# analog_channel.net
KiCad netlist of a schematic drawn in Altium Designer
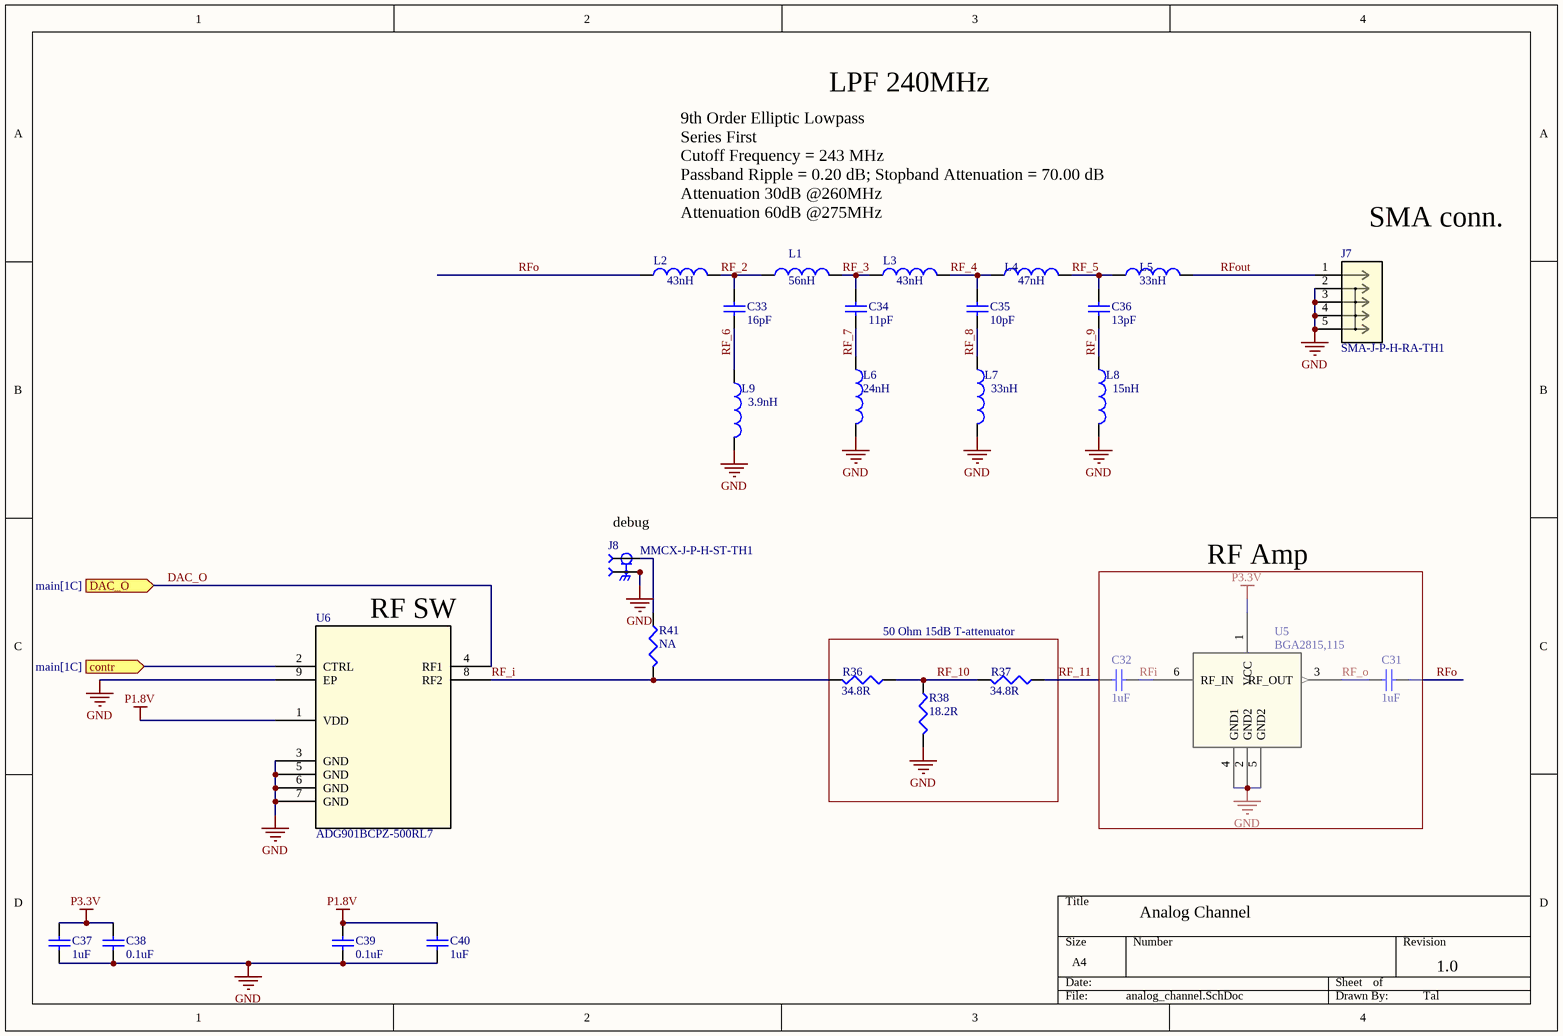
[diagram p0: analog_channel.SchDoc]

(export (version "E")
  (design (tool "Eeschema 10.0.6"))
  (components
    (comp (ref "C31")
      (value "1uF 25V")
      (footprint "Landa_PCB:C0402")
      (description "CAP CER 1uF 25V X5R 0402")
      (fields
        (field (name "MANUFACTURER PART NUMBER") "C1005C0G1H6R8D")
        (field (name "MANUFACTURER") "TDK Corporation")
        (field (name "CAPACITANCE") "1uF")
      )
      (libsource (lib "L_SCH_C") (part "CAP CER 6.8pF 50V NP0 0402"))
    )
    (comp (ref "C32")
      (value "1uF 25V")
      (footprint "Landa_PCB:C0402")
      (description "CAP CER 1uF 25V X5R 0402")
      (fields
        (field (name "MANUFACTURER PART NUMBER") "C1005C0G1H6R8D")
        (field (name "MANUFACTURER") "TDK Corporation")
        (field (name "CAPACITANCE") "1uF")
      )
      (libsource (lib "L_SCH_C") (part "CAP CER 6.8pF 50V NP0 0402"))
    )
    (comp (ref "C33")
      (value "16pF 50V")
      (footprint "Landa_PCB:C0402")
      (description "CAP CER 16PF 50V 5% NP0 0402")
      (fields
        (field (name "MANUFACTURER") "TDK Corporation")
        (field (name "MANUFACTURER PART NUMBER") "C1005C0G1H200J")
        (field (name "CAPACITANCE") "16pF")
      )
      (libsource (lib "L_SCH_C") (part "CAP CER 20pF 50V 5% NP0 0402"))
    )
    (comp (ref "C34")
      (value "11pF 50V")
      (footprint "Landa_PCB:C0402")
      (description "CAP CER 11PF 50V 5% NP0 0402")
      (fields
        (field (name "MANUFACTURER") "TDK Corporation")
        (field (name "MANUFACTURER PART NUMBER") "C1005C0G1H200J")
        (field (name "CAPACITANCE") "11pF")
      )
      (libsource (lib "L_SCH_C") (part "CAP CER 20pF 50V 5% NP0 0402"))
    )
    (comp (ref "C35")
      (value "10pF 50V")
      (footprint "Landa_PCB:C0402")
      (description "CAP CER 10PF 50V 5% NP0 0402")
      (fields
        (field (name "MANUFACTURER") "TDK Corporation")
        (field (name "MANUFACTURER PART NUMBER") "C1005C0G1H200J")
        (field (name "CAPACITANCE") "10pF")
      )
      (libsource (lib "L_SCH_C") (part "CAP CER 20pF 50V 5% NP0 0402"))
    )
    (comp (ref "C36")
      (value "13pF 50V")
      (footprint "Landa_PCB:C0402")
      (description "CAP CER 13PF 50V 5% NP0 0402")
      (fields
        (field (name "MANUFACTURER") "TDK Corporation")
        (field (name "MANUFACTURER PART NUMBER") "C1005C0G1H200J")
        (field (name "CAPACITANCE") "13pF")
      )
      (libsource (lib "L_SCH_C") (part "CAP CER 20pF 50V 5% NP0 0402"))
    )
    (comp (ref "C37")
      (value "1uF 25V")
      (footprint "Landa_PCB:C0402")
      (description "CAP CER 1uF 25V X5R 0402")
      (fields
        (field (name "MANUFACTURER PART NUMBER") "C1005C0G1H6R8D")
        (field (name "MANUFACTURER") "TDK Corporation")
        (field (name "CAPACITANCE") "1uF")
      )
      (libsource (lib "L_SCH_C") (part "CAP CER 6.8pF 50V NP0 0402"))
    )
    (comp (ref "C38")
      (value "0.1uF 50V")
      (footprint "Landa_PCB:C0402")
      (description "CAP CER 0.1uF 50V NP0 0402")
      (fields
        (field (name "MANUFACTURER PART NUMBER") "C1005C0G1H6R8D")
        (field (name "MANUFACTURER") "TDK Corporation")
        (field (name "CAPACITANCE") "0.1uF")
      )
      (libsource (lib "L_SCH_C") (part "CAP CER 6.8pF 50V NP0 0402"))
    )
    (comp (ref "C39")
      (value "0.1uF 50V")
      (footprint "Landa_PCB:C0402")
      (description "CAP CER 0.1uF 50V NP0 0402")
      (fields
        (field (name "MANUFACTURER PART NUMBER") "C1005C0G1H6R8D")
        (field (name "MANUFACTURER") "TDK Corporation")
        (field (name "CAPACITANCE") "0.1uF")
      )
      (libsource (lib "L_SCH_C") (part "CAP CER 6.8pF 50V NP0 0402"))
    )
    (comp (ref "C40")
      (value "1uF 25V")
      (footprint "Landa_PCB:C0402")
      (description "CAP CER 1uF 25V X5R 0402")
      (fields
        (field (name "MANUFACTURER PART NUMBER") "C1005C0G1H6R8D")
        (field (name "MANUFACTURER") "TDK Corporation")
        (field (name "CAPACITANCE") "1uF")
      )
      (libsource (lib "L_SCH_C") (part "CAP CER 6.8pF 50V NP0 0402"))
    )
    (comp (ref "J7")
      (value "SMA-J-P-H-RA-TH1")
      (footprint "CONN_SMA-J-P-H-RA-TH1_SAI")
      (description "No Description Available")
      (fields (field (name "COPYRIGHT") "Copyright (C) 2023 Ultra Librarian. All rights reserved."))
      (libsource (lib "SMA-J-P-H-RA-TH1") (part "SMA-J-P-H-RA-TH1"))
    )
    (comp (ref "J8")
      (value "MMCX-J-P-H-ST-TH1")
      (footprint "SAMTEC_MMCX-J-P-H-ST-TH1")
      (description "MMCX STRAIGHT, THROUGH HOLE JACK- 50 OHM")
      (fields (field (name "MF") "Samtec"))
      (libsource (lib "MMCX-J-P-H-ST-TH1") (part "MMCX-J-P-H-ST-TH1"))
    )
    (comp (ref "L1")
      (value "56nH")
      (footprint "0402-A")
      (description "Inductor")
      (fields (field (name "PUBLISHER") "Altium Limited"))
      (libsource (lib "Miscellaneous Devices") (part "Inductor"))
    )
    (comp (ref "L2")
      (value "43nH")
      (footprint "0402-A")
      (description "Inductor")
      (fields (field (name "PUBLISHER") "Altium Limited"))
      (libsource (lib "Miscellaneous Devices") (part "Inductor"))
    )
    (comp (ref "L3")
      (value "43nH")
      (footprint "0402-A")
      (description "Inductor")
      (fields (field (name "PUBLISHER") "Altium Limited"))
      (libsource (lib "Miscellaneous Devices") (part "Inductor"))
    )
    (comp (ref "L4")
      (value "47nH")
      (footprint "0402-A")
      (description "Inductor")
      (fields (field (name "PUBLISHER") "Altium Limited"))
      (libsource (lib "Miscellaneous Devices") (part "Inductor"))
    )
    (comp (ref "L5")
      (value "33nH")
      (footprint "0402-A")
      (description "Inductor")
      (fields (field (name "PUBLISHER") "Altium Limited"))
      (libsource (lib "Miscellaneous Devices") (part "Inductor"))
    )
    (comp (ref "L6")
      (value "24nH")
      (footprint "0402-A")
      (description "Inductor")
      (fields (field (name "PUBLISHER") "Altium Limited"))
      (libsource (lib "Miscellaneous Devices") (part "Inductor"))
    )
    (comp (ref "L7")
      (value "33nH")
      (footprint "0402-A")
      (description "Inductor")
      (fields (field (name "PUBLISHER") "Altium Limited"))
      (libsource (lib "Miscellaneous Devices") (part "Inductor"))
    )
    (comp (ref "L8")
      (value "15nH")
      (footprint "0402-A")
      (description "Inductor")
      (fields (field (name "PUBLISHER") "Altium Limited"))
      (libsource (lib "Miscellaneous Devices") (part "Inductor"))
    )
    (comp (ref "L9")
      (value "3.9nH")
      (footprint "0402-A")
      (description "Inductor")
      (fields (field (name "PUBLISHER") "Altium Limited"))
      (libsource (lib "Miscellaneous Devices") (part "Inductor"))
    )
    (comp (ref "R36")
      (value "34.8R")
      (footprint "r0402")
      (description "RES 34.8 OHM 1/10W 1% 0402 SMD")
      (fields
        (field (name "MANUFACTURER PART NUMBER") "ERJ-2RKF1000X")
        (field (name "MANUFACTURER") "Panasonic Electronic Components")
      )
      (libsource (lib "L_SCH_R") (part "RES 100 OHM 1/10W 1% 0402 SMD"))
    )
    (comp (ref "R37")
      (value "34.8R")
      (footprint "r0402")
      (description "RES 34.8 OHM 1/10W 1% 0402 SMD")
      (fields
        (field (name "MANUFACTURER PART NUMBER") "ERJ-2RKF1000X")
        (field (name "MANUFACTURER") "Panasonic Electronic Components")
      )
      (libsource (lib "L_SCH_R") (part "RES 100 OHM 1/10W 1% 0402 SMD"))
    )
    (comp (ref "R38")
      (value "18.2R")
      (footprint "r0402")
      (description "RES 18.2 OHM 1/10W 1% 0402 SMD")
      (fields
        (field (name "MANUFACTURER PART NUMBER") "ERJ-2RKF1000X")
        (field (name "MANUFACTURER") "Panasonic Electronic Components")
      )
      (libsource (lib "L_SCH_R") (part "RES 100 OHM 1/10W 1% 0402 SMD"))
    )
    (comp (ref "R41")
      (value "NA")
      (footprint "r0402")
      (description "RES 0 OHM 1/10W 1% 0402 SMD")
      (fields
        (field (name "MANUFACTURER PART NUMBER") "ERJ-2RKF1000X")
        (field (name "MANUFACTURER") "Panasonic Electronic Components")
      )
      (libsource (lib "L_SCH_R") (part "RES 100 OHM 1/10W 1% 0402 SMD"))
    )
    (comp (ref "U5")
      (value "BGA2815,115")
      (footprint "SOT_2815,115_NXP")
      (description "No Description Available")
      (fields (field (name "COPYRIGHT") "Copyright (C) 2023 Ultra Librarian. All rights reserved."))
      (libsource (lib "BGA2815,115") (part "BGA2815,115"))
    )
    (comp (ref "U6")
      (value "ADG901BCPZ-500RL7")
      (footprint "CP_8_2_ADI")
      (description "No Description Available")
      (fields (field (name "COPYRIGHT") "Copyright (C) 2023 Ultra Librarian. All rights reserved."))
      (libsource (lib "ADG901BCPZ-500RL7") (part "ADG901BCPZ-500RL7"))
    )
  )
  (nets
    (net (code "1") (name "/DAC_O") (class "Default")
      (node (ref "U6") (pin "4") (pinfunction "RF1_4") (pintype "passive"))
    )
    (net (code "2") (name "/RF_2") (class "Default")
      (node (ref "C33") (pin "1") (pinfunction "1_1") (pintype "passive"))
      (node (ref "L1") (pin "1") (pinfunction "1_1") (pintype "passive"))
      (node (ref "L2") (pin "2") (pinfunction "2_2") (pintype "passive"))
    )
    (net (code "3") (name "/RF_3") (class "Default")
      (node (ref "C34") (pin "1") (pinfunction "1_1") (pintype "passive"))
      (node (ref "L1") (pin "2") (pinfunction "2_2") (pintype "passive"))
      (node (ref "L3") (pin "1") (pinfunction "1_1") (pintype "passive"))
    )
    (net (code "4") (name "/RF_4") (class "Default")
      (node (ref "C35") (pin "1") (pinfunction "1_1") (pintype "passive"))
      (node (ref "L3") (pin "2") (pinfunction "2_2") (pintype "passive"))
      (node (ref "L4") (pin "1") (pinfunction "1_1") (pintype "passive"))
    )
    (net (code "5") (name "/RF_5") (class "Default")
      (node (ref "C36") (pin "1") (pinfunction "1_1") (pintype "passive"))
      (node (ref "L4") (pin "2") (pinfunction "2_2") (pintype "passive"))
      (node (ref "L5") (pin "1") (pinfunction "1_1") (pintype "passive"))
    )
    (net (code "6") (name "/RF_6") (class "Default")
      (node (ref "C33") (pin "2") (pinfunction "2_2") (pintype "passive"))
      (node (ref "L9") (pin "1") (pinfunction "1_1") (pintype "passive"))
    )
    (net (code "7") (name "/RF_7") (class "Default")
      (node (ref "C34") (pin "2") (pinfunction "2_2") (pintype "passive"))
      (node (ref "L6") (pin "1") (pinfunction "1_1") (pintype "passive"))
    )
    (net (code "8") (name "/RF_8") (class "Default")
      (node (ref "C35") (pin "2") (pinfunction "2_2") (pintype "passive"))
      (node (ref "L7") (pin "1") (pinfunction "1_1") (pintype "passive"))
    )
    (net (code "9") (name "/RF_9") (class "Default")
      (node (ref "C36") (pin "2") (pinfunction "2_2") (pintype "passive"))
      (node (ref "L8") (pin "1") (pinfunction "1_1") (pintype "passive"))
    )
    (net (code "10") (name "/RF_10") (class "Default")
      (node (ref "R36") (pin "1") (pinfunction "1_1") (pintype "passive"))
      (node (ref "R37") (pin "2") (pinfunction "2_2") (pintype "passive"))
      (node (ref "R38") (pin "1") (pinfunction "1_1") (pintype "passive"))
    )
    (net (code "11") (name "/RF_11") (class "Default")
      (node (ref "C32") (pin "1") (pinfunction "1_1") (pintype "passive"))
      (node (ref "R37") (pin "1") (pinfunction "1_1") (pintype "passive"))
    )
    (net (code "12") (name "/RF_i") (class "Default")
      (node (ref "R36") (pin "2") (pinfunction "2_2") (pintype "passive"))
      (node (ref "R41") (pin "2") (pinfunction "2_2") (pintype "passive"))
      (node (ref "U6") (pin "8") (pinfunction "RF2_8") (pintype "passive"))
    )
    (net (code "13") (name "/RF_o") (class "Default")
      (node (ref "C31") (pin "1") (pinfunction "1_1") (pintype "passive"))
      (node (ref "U5") (pin "3") (pinfunction "RF_OUT_3") (pintype "output"))
    )
    (net (code "14") (name "/RFi") (class "Default")
      (node (ref "C32") (pin "2") (pinfunction "2_2") (pintype "passive"))
      (node (ref "U5") (pin "6") (pinfunction "RF_IN_6") (pintype "passive"))
    )
    (net (code "15") (name "/RFo") (class "Default")
      (node (ref "C31") (pin "2") (pinfunction "2_2") (pintype "passive"))
      (node (ref "L2") (pin "1") (pinfunction "1_1") (pintype "passive"))
    )
    (net (code "16") (name "/RFout") (class "Default")
      (node (ref "J7") (pin "1") (pinfunction "1_1") (pintype "passive"))
      (node (ref "L5") (pin "2") (pinfunction "2_2") (pintype "passive"))
    )
    (net (code "17") (name "/contr") (class "Default")
      (node (ref "U6") (pin "2") (pinfunction "CTRL_2") (pintype "passive"))
    )
    (net (code "18") (name "GND") (class "Default")
      (node (ref "C37") (pin "1") (pinfunction "1_1") (pintype "passive"))
      (node (ref "C38") (pin "1") (pinfunction "1_1") (pintype "passive"))
      (node (ref "C39") (pin "1") (pinfunction "1_1") (pintype "passive"))
      (node (ref "C40") (pin "1") (pinfunction "1_1") (pintype "passive"))
      (node (ref "J7") (pin "2") (pinfunction "2_2") (pintype "passive"))
      (node (ref "J7") (pin "3") (pinfunction "3_3") (pintype "passive"))
      (node (ref "J7") (pin "4") (pinfunction "4_4") (pintype "passive"))
      (node (ref "J7") (pin "5") (pinfunction "5_5") (pintype "passive"))
      (node (ref "J8") (pin "S1") (pinfunction "2_S1") (pintype "passive"))
      (node (ref "J8") (pin "S2") (pinfunction "2_S2") (pintype "passive"))
      (node (ref "J8") (pin "S3") (pinfunction "2_S3") (pintype "passive"))
      (node (ref "J8") (pin "S4") (pinfunction "2_S4") (pintype "passive"))
      (node (ref "L6") (pin "2") (pinfunction "2_2") (pintype "passive"))
      (node (ref "L7") (pin "2") (pinfunction "2_2") (pintype "passive"))
      (node (ref "L8") (pin "2") (pinfunction "2_2") (pintype "passive"))
      (node (ref "L9") (pin "2") (pinfunction "2_2") (pintype "passive"))
      (node (ref "R38") (pin "2") (pinfunction "2_2") (pintype "passive"))
      (node (ref "U5") (pin "2") (pinfunction "GND2_2") (pintype "passive"))
      (node (ref "U5") (pin "4") (pinfunction "GND1_4") (pintype "passive"))
      (node (ref "U5") (pin "5") (pinfunction "GND2_5") (pintype "passive"))
      (node (ref "U6") (pin "3") (pinfunction "GND_3") (pintype "passive"))
      (node (ref "U6") (pin "5") (pinfunction "GND_5") (pintype "passive"))
      (node (ref "U6") (pin "6") (pinfunction "GND_6") (pintype "passive"))
      (node (ref "U6") (pin "7") (pinfunction "GND_7") (pintype "passive"))
      (node (ref "U6") (pin "9") (pinfunction "EP_9") (pintype "passive"))
    )
    (net (code "19") (name "Net-(J8-Pad1)") (class "Default")
      (node (ref "J8") (pin "1") (pinfunction "1_1") (pintype "passive"))
      (node (ref "R41") (pin "1") (pinfunction "1_1") (pintype "passive"))
    )
    (net (code "20") (name "P1.8V") (class "Default")
      (node (ref "C39") (pin "2") (pinfunction "2_2") (pintype "passive"))
      (node (ref "C40") (pin "2") (pinfunction "2_2") (pintype "passive"))
      (node (ref "U6") (pin "1") (pinfunction "VDD_1") (pintype "power_in"))
    )
    (net (code "21") (name "P3.3V") (class "Default")
      (node (ref "C37") (pin "2") (pinfunction "2_2") (pintype "passive"))
      (node (ref "C38") (pin "2") (pinfunction "2_2") (pintype "passive"))
      (node (ref "U5") (pin "1") (pinfunction "VCC_1") (pintype "power_in"))
    )
  )
)
